# Regulador.net
KiCad netlist of a schematic drawn in Altium Designer
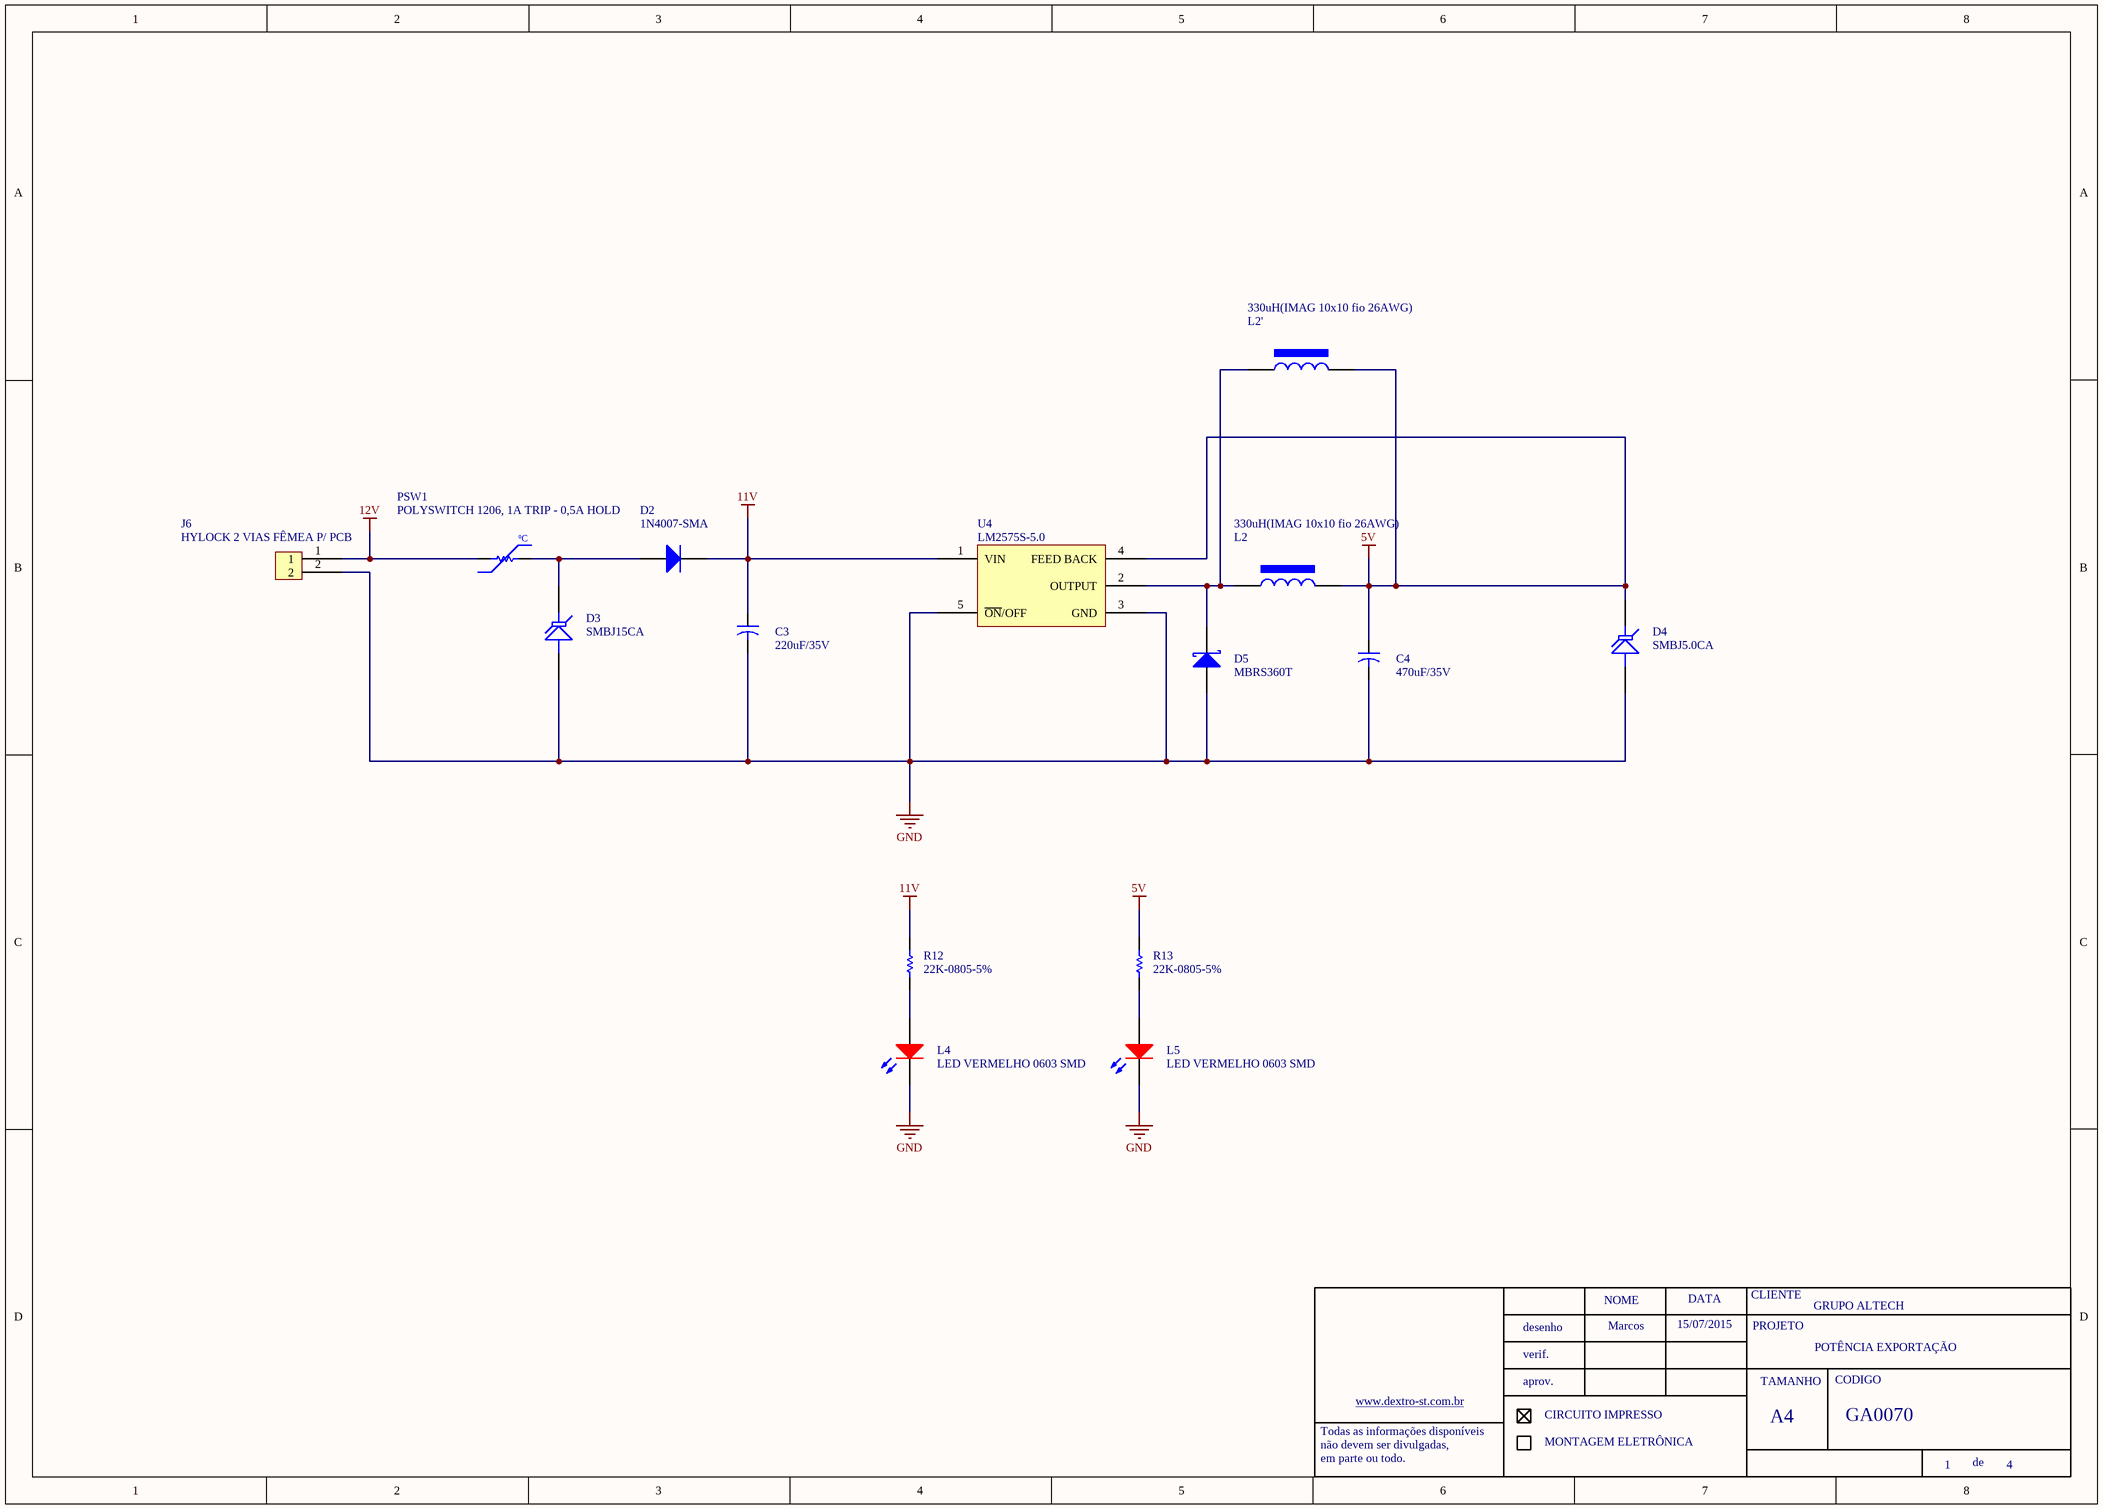
[diagram p0: Regulador.SchDoc]

(export (version "E")
  (design (tool "Eeschema 10.0.6"))
  (components
    (comp (ref "C3")
      (value "220uF/35V")
      (footprint "CAP POL 8x12mm")
      (description "2200uF/50V")
      (libsource (lib "AquinoLib") (part "2200uF/50V"))
    )
    (comp (ref "C4")
      (value "470uF/35V")
      (footprint "CAP POL 8x12mm")
      (description "470uF/50V")
      (libsource (lib "AquinoLib") (part "470uF/50V"))
    )
    (comp (ref "D2")
      (value "1N4007-SMA")
      (footprint "DO-214AA")
      (description "1N4007")
      (libsource (lib "AquinoLib") (part "1N4007"))
    )
    (comp (ref "D3")
      (value "SMBJ15CA")
      (footprint "DO-214AA")
      (description "SMBJ30.0A")
      (libsource (lib "AquinoLib") (part "SMBJ30.0A"))
    )
    (comp (ref "D4")
      (value "SMBJ5.0CA")
      (footprint "DO-214AA")
      (description "SMBJ5.0A")
      (libsource (lib "AquinoLib") (part "SMBJ5.0A"))
    )
    (comp (ref "D5")
      (value "MBRS360T")
      (footprint "DO-214AA")
      (description "1N5819-SOD80")
      (libsource (lib "AquinoLib") (part "1N5819-SOD80"))
    )
    (comp (ref "J6")
      (value "HYLOCK 2 VIAS FÊMEA P/ PCB")
      (footprint "CONECTOR HYLOCK 2 VIAS")
      (description "PCMC2-2")
      (libsource (lib "AquinoLib") (part "PCMC2-2"))
    )
    (comp (ref "L2")
      (value "330uH(IMAG 10x10 fio 26AWG)")
      (footprint "INDUTOR 47mH")
      (description "1mH-CNF15-26 AWG")
      (libsource (lib "AquinoLib") (part "indutor 1mH CNF15"))
    )
    (comp (ref "L2'")
      (value "330uH(IMAG 10x10 fio 26AWG)")
      (footprint "INDUTOR LOCO")
      (description "1mH-CNF15-26 AWG")
      (libsource (lib "AquinoLib") (part "indutor 1mH CNF15"))
    )
    (comp (ref "L4")
      (value "LED VERMELHO 0603 SMD")
      (footprint "LED 1206")
      (libsource (lib "AquinoLib") (part "LED VERMELHO 0603 SMD"))
    )
    (comp (ref "L5")
      (value "LED VERMELHO 0603 SMD")
      (footprint "LED 1206")
      (libsource (lib "AquinoLib") (part "LED VERMELHO 0603 SMD"))
    )
    (comp (ref "PSW1")
      (value "POLYSWITCH 1206, 1A TRIP - 0,5A HOLD")
      (footprint "1206-REVISADO ONDA")
      (description "NANOSMDC020F-2")
      (libsource (lib "AquinoLib") (part "POLYSWITCH 200mA"))
    )
    (comp (ref "R12")
      (value "22K-0805-5%")
      (footprint "0805-REVISADO ONDA")
      (libsource (lib "AquinoLib") (part "22K-0805-5%"))
    )
    (comp (ref "R13")
      (value "22K-0805-5%")
      (footprint "0805-REVISADO ONDA")
      (libsource (lib "AquinoLib") (part "22K-0805-5%"))
    )
    (comp (ref "U4")
      (value "LM2575S-5.0")
      (footprint "TO-263-5")
      (description "LM2596S-ADJ")
      (libsource (lib "AquinoLib") (part "LM2596S-ADJ"))
    )
  )
  (nets
    (net (code "1") (name "5V") (class "Default")
      (node (ref "C4") (pin "1") (pinfunction "1_1") (pintype "passive"))
      (node (ref "D4") (pin "2") (pinfunction "K_2") (pintype "passive"))
      (node (ref "L2") (pin "1") (pinfunction "1_1") (pintype "passive"))
      (node (ref "L2'") (pin "1") (pinfunction "1_1") (pintype "passive"))
      (node (ref "R13") (pin "2") (pinfunction "2_2") (pintype "passive"))
      (node (ref "U4") (pin "4") (pinfunction "FEED_BACK_4") (pintype "passive"))
    )
    (net (code "2") (name "11V") (class "Default")
      (node (ref "C3") (pin "1") (pinfunction "1_1") (pintype "passive"))
      (node (ref "D2") (pin "2") (pinfunction "K_2") (pintype "passive"))
      (node (ref "R12") (pin "2") (pinfunction "2_2") (pintype "passive"))
      (node (ref "U4") (pin "1") (pinfunction "VIN_1") (pintype "passive"))
    )
    (net (code "3") (name "12V") (class "Default")
      (node (ref "J6") (pin "1") (pinfunction "1_1") (pintype "passive"))
      (node (ref "PSW1") (pin "1") (pinfunction "1_1") (pintype "passive"))
    )
    (net (code "4") (name "GND") (class "Default")
      (node (ref "C3") (pin "2") (pinfunction "2_2") (pintype "passive"))
      (node (ref "C4") (pin "2") (pinfunction "2_2") (pintype "passive"))
      (node (ref "D3") (pin "1") (pinfunction "A_1") (pintype "passive"))
      (node (ref "D4") (pin "1") (pinfunction "A_1") (pintype "passive"))
      (node (ref "D5") (pin "1") (pinfunction "A_1") (pintype "passive"))
      (node (ref "J6") (pin "2") (pinfunction "2_2") (pintype "passive"))
      (node (ref "L4") (pin "2") (pinfunction "K_2") (pintype "passive"))
      (node (ref "L5") (pin "2") (pinfunction "K_2") (pintype "passive"))
      (node (ref "U4") (pin "3") (pinfunction "GND_3") (pintype "passive"))
      (node (ref "U4") (pin "5") (pinfunction "~{ON}/OFF_5") (pintype "passive"))
    )
    (net (code "5") (name "Net-(D2-A)") (class "Default")
      (node (ref "D2") (pin "1") (pinfunction "A_1") (pintype "passive"))
      (node (ref "D3") (pin "2") (pinfunction "K_2") (pintype "passive"))
      (node (ref "PSW1") (pin "2") (pinfunction "2_2") (pintype "passive"))
    )
    (net (code "6") (name "Net-(D5-K)") (class "Default")
      (node (ref "D5") (pin "2") (pinfunction "K_2") (pintype "passive"))
      (node (ref "L2") (pin "2") (pinfunction "2_2") (pintype "passive"))
      (node (ref "L2'") (pin "2") (pinfunction "2_2") (pintype "passive"))
      (node (ref "U4") (pin "2") (pinfunction "OUTPUT_2") (pintype "passive"))
    )
    (net (code "7") (name "Net-(L4-A)") (class "Default")
      (node (ref "L4") (pin "1") (pinfunction "A_1") (pintype "passive"))
      (node (ref "R12") (pin "1") (pinfunction "1_1") (pintype "passive"))
    )
    (net (code "8") (name "Net-(L5-A)") (class "Default")
      (node (ref "L5") (pin "1") (pinfunction "A_1") (pintype "passive"))
      (node (ref "R13") (pin "1") (pinfunction "1_1") (pintype "passive"))
    )
  )
)
